# Input.net
KiCad netlist of a schematic drawn in Altium Designer
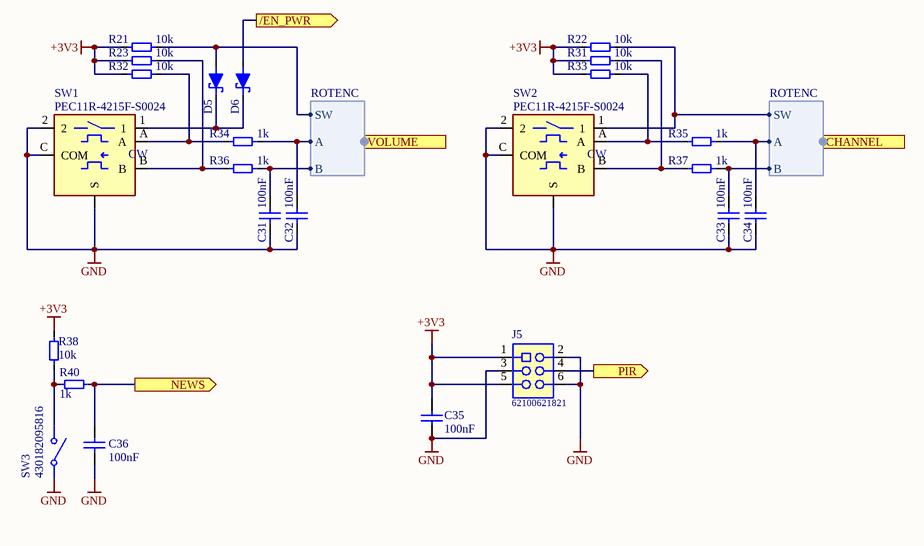
[diagram p0: Input.SchDoc]

(export (version "E")
  (design (tool "Eeschema 10.0.6"))
  (components
    (comp (ref "C31")
      (value "100nF")
      (footprint "0603-C-N")
      (description "WCAP-CSGP Multilayer Ceramic Chip Capacitor, General Purpose, size 0603, X7R, 100nF, 50VDC")
      (fields (field (name "TOLERANCE") "10%") (field (name "JLCPCB PART #") "C14663"))
      (libsource (lib "7c7 Engineering") (part "CAP-NP-2"))
    )
    (comp (ref "C32")
      (value "100nF")
      (footprint "0603-C-N")
      (description "WCAP-CSGP Multilayer Ceramic Chip Capacitor, General Purpose, size 0603, X7R, 100nF, 50VDC")
      (fields (field (name "TOLERANCE") "10%") (field (name "JLCPCB PART #") "C14663"))
      (libsource (lib "7c7 Engineering") (part "CAP-NP-2"))
    )
    (comp (ref "C33")
      (value "100nF")
      (footprint "0603-C-N")
      (description "WCAP-CSGP Multilayer Ceramic Chip Capacitor, General Purpose, size 0603, X7R, 100nF, 50VDC")
      (fields (field (name "TOLERANCE") "10%") (field (name "JLCPCB PART #") "C14663"))
      (libsource (lib "7c7 Engineering") (part "CAP-NP-2"))
    )
    (comp (ref "C34")
      (value "100nF")
      (footprint "0603-C-N")
      (description "WCAP-CSGP Multilayer Ceramic Chip Capacitor, General Purpose, size 0603, X7R, 100nF, 50VDC")
      (fields (field (name "TOLERANCE") "10%") (field (name "JLCPCB PART #") "C14663"))
      (libsource (lib "7c7 Engineering") (part "CAP-NP-2"))
    )
    (comp (ref "C35")
      (value "100nF")
      (footprint "0603-C-N")
      (description "WCAP-CSGP Multilayer Ceramic Chip Capacitor, General Purpose, size 0603, X7R, 100nF, 50VDC")
      (fields (field (name "TOLERANCE") "10%") (field (name "JLCPCB PART #") "C14663"))
      (libsource (lib "7c7 Engineering") (part "CAP-NP-2"))
    )
    (comp (ref "C36")
      (value "100nF")
      (footprint "0603-C-N")
      (description "WCAP-CSGP Multilayer Ceramic Chip Capacitor, General Purpose, size 0603, X7R, 100nF, 50VDC")
      (fields (field (name "TOLERANCE") "10%") (field (name "JLCPCB PART #") "C14663"))
      (libsource (lib "7c7 Engineering") (part "CAP-NP-2"))
    )
    (comp (ref "D5")
      (value "1PS79SB30,115")
      (footprint "FP-SOD523-MFG")
      (description "VR=40V IF=200mA 20pF")
      (fields (field (name "JLCPCB PART #") "C426690"))
      (libsource (lib "7c7 Engineering") (part "DIODE-SKY-2"))
    )
    (comp (ref "D6")
      (value "1PS79SB30,115")
      (footprint "FP-SOD523-MFG")
      (description "VR=40V IF=200mA 20pF")
      (fields (field (name "JLCPCB PART #") "C426690"))
      (libsource (lib "7c7 Engineering") (part "DIODE-SKY-2"))
    )
    (comp (ref "J5")
      (value "62100621821")
      (footprint "62100621821")
      (description "WR-PHD Socket Header, SMT, pitch 2mm, Dual Row, Vertical, 6p")
      (fields (field (name "MANUFACTURER") "Wurth Elektronik"))
      (libsource (lib "7c7 Engineering") (part "Symbol"))
    )
    (comp (ref "R21")
      (value "10k")
      (footprint "0603-R-N")
      (description "Chip Resistor, Thick Film, General Purpose, 0603, 100mW, 50V, 10 kOhm, +/-1%")
      (fields (field (name "JLCPCB PART #") "C25804") (field (name "TOLERANCE") "1%"))
      (libsource (lib "") (part "RES_1"))
    )
    (comp (ref "R22")
      (value "10k")
      (footprint "0603-R-N")
      (description "Chip Resistor, Thick Film, General Purpose, 0603, 100mW, 50V, 10 kOhm, +/-1%")
      (fields (field (name "JLCPCB PART #") "C25804") (field (name "TOLERANCE") "1%"))
      (libsource (lib "") (part "RES_1"))
    )
    (comp (ref "R23")
      (value "10k")
      (footprint "0603-R-N")
      (description "Chip Resistor, Thick Film, General Purpose, 0603, 100mW, 50V, 10 kOhm, +/-1%")
      (fields (field (name "JLCPCB PART #") "C25804") (field (name "TOLERANCE") "1%"))
      (libsource (lib "7c7 Engineering") (part "RES"))
    )
    (comp (ref "R31")
      (value "10k")
      (footprint "0603-R-N")
      (description "Chip Resistor, Thick Film, General Purpose, 0603, 100mW, 50V, 10 kOhm, +/-1%")
      (fields (field (name "JLCPCB PART #") "C25804") (field (name "TOLERANCE") "1%"))
      (libsource (lib "7c7 Engineering") (part "RES"))
    )
    (comp (ref "R32")
      (value "10k")
      (footprint "0603-R-N")
      (description "Chip Resistor, Thick Film, General Purpose, 0603, 100mW, 50V, 10 kOhm, +/-1%")
      (fields (field (name "JLCPCB PART #") "C25804") (field (name "TOLERANCE") "1%"))
      (libsource (lib "7c7 Engineering") (part "RES"))
    )
    (comp (ref "R33")
      (value "10k")
      (footprint "0603-R-N")
      (description "Chip Resistor, Thick Film, General Purpose, 0603, 100mW, 50V, 10 kOhm, +/-1%")
      (fields (field (name "JLCPCB PART #") "C25804") (field (name "TOLERANCE") "1%"))
      (libsource (lib "7c7 Engineering") (part "RES"))
    )
    (comp (ref "R34")
      (value "1k")
      (footprint "0603-R-N")
      (description "Chip Resistor, Thick Film, General Purpose, 0603, 100mW, 50V, 1 kOhm, +/-1%")
      (fields (field (name "JLCPCB PART #") "C21190") (field (name "TOLERANCE") "1%"))
      (libsource (lib "") (part "RES_1"))
    )
    (comp (ref "R35")
      (value "1k")
      (footprint "0603-R-N")
      (description "Chip Resistor, Thick Film, General Purpose, 0603, 100mW, 50V, 1 kOhm, +/-1%")
      (fields (field (name "JLCPCB PART #") "C21190") (field (name "TOLERANCE") "1%"))
      (libsource (lib "") (part "RES_1"))
    )
    (comp (ref "R36")
      (value "1k")
      (footprint "0603-R-N")
      (description "Chip Resistor, Thick Film, General Purpose, 0603, 100mW, 50V, 1 kOhm, +/-1%")
      (fields (field (name "JLCPCB PART #") "C21190") (field (name "TOLERANCE") "1%"))
      (libsource (lib "") (part "RES_1"))
    )
    (comp (ref "R37")
      (value "1k")
      (footprint "0603-R-N")
      (description "Chip Resistor, Thick Film, General Purpose, 0603, 100mW, 50V, 1 kOhm, +/-1%")
      (fields (field (name "JLCPCB PART #") "C21190") (field (name "TOLERANCE") "1%"))
      (libsource (lib "") (part "RES_1"))
    )
    (comp (ref "R38")
      (value "10k")
      (footprint "0603-R-N")
      (description "Chip Resistor, Thick Film, General Purpose, 0603, 100mW, 50V, 10 kOhm, +/-1%")
      (fields (field (name "JLCPCB PART #") "C25804") (field (name "TOLERANCE") "1%"))
      (libsource (lib "") (part "RES_1"))
    )
    (comp (ref "R40")
      (value "1k")
      (footprint "0603-R-N")
      (description "Chip Resistor, Thick Film, General Purpose, 0603, 100mW, 50V, 1 kOhm, +/-1%")
      (fields (field (name "JLCPCB PART #") "C21190") (field (name "TOLERANCE") "1%"))
      (libsource (lib "") (part "RES_2"))
    )
    (comp (ref "SW1")
      (value "PEC11R-4215F-S0024")
      (footprint "PEC11R-4215F-S0024")
      (description "Incremental Encoder 24 PPR 2 Bit Quadrature 5VDC at 10 mA IP40 PCB Mount 60RPM")
      (fields (field (name "JLCPCB PART #") "C143790"))
      (libsource (lib "7c7 Engineering") (part "482024764004"))
    )
    (comp (ref "SW2")
      (value "PEC11R-4215F-S0024")
      (footprint "PEC11R-4215F-S0024")
      (description "Incremental Encoder 24 PPR 2 Bit Quadrature 5VDC at 10 mA IP40 PCB Mount 60RPM")
      (fields (field (name "JLCPCB PART #") "C143790"))
      (libsource (lib "7c7 Engineering") (part "482024764004"))
    )
    (comp (ref "SW3")
      (value "430182095816")
      (footprint "WS-TASV_L6W6H9.5_4301x20958x6")
      (description "WS-TASV SMT Tact Switch, 12VDC, 50mA, 160g, height 9.5mm")
      (fields (field (name "MANUFACTURER") "Wurth Elektronik") (field (name "JLCPCB PART #") "C285487"))
      (libsource (lib "7c7 Engineering") (part "SW_MOM"))
    )
  )
  (nets
    (net (code "2") (name "+3V3") (class "Default")
      (node (ref "C35") (pin "2") (pinfunction "2_2") (pintype "passive"))
      (node (ref "J5") (pin "1") (pinfunction "1_1") (pintype "passive"))
      (node (ref "J5") (pin "5") (pinfunction "5_5") (pintype "passive"))
      (node (ref "R21") (pin "1") (pinfunction "1_1") (pintype "passive"))
      (node (ref "R22") (pin "1") (pinfunction "1_1") (pintype "passive"))
      (node (ref "R23") (pin "2") (pinfunction "2_2") (pintype "passive"))
      (node (ref "R31") (pin "2") (pinfunction "2_2") (pintype "passive"))
      (node (ref "R32") (pin "2") (pinfunction "2_2") (pintype "passive"))
      (node (ref "R33") (pin "2") (pinfunction "2_2") (pintype "passive"))
      (node (ref "R38") (pin "2") (pinfunction "2_2") (pintype "passive"))
    )
    (net (code "3") (name "/NEWS") (class "Default")
      (node (ref "C36") (pin "2") (pinfunction "2_2") (pintype "passive"))
      (node (ref "R40") (pin "2") (pinfunction "2_2") (pintype "passive"))
    )
    (net (code "4") (name "/PIR") (class "Default")
      (node (ref "J5") (pin "4") (pinfunction "4_4") (pintype "passive"))
    )
    (net (code "6") (name "/{slash}EN_PWR") (class "Default")
      (node (ref "D6") (pin "2") (pinfunction "A_2") (pintype "passive"))
    )
    (net (code "7") (name "GND") (class "Default")
      (node (ref "C31") (pin "1") (pinfunction "1_1") (pintype "passive"))
      (node (ref "C32") (pin "1") (pinfunction "1_1") (pintype "passive"))
      (node (ref "C33") (pin "1") (pinfunction "1_1") (pintype "passive"))
      (node (ref "C34") (pin "1") (pinfunction "1_1") (pintype "passive"))
      (node (ref "C35") (pin "1") (pinfunction "1_1") (pintype "passive"))
      (node (ref "C36") (pin "1") (pinfunction "1_1") (pintype "passive"))
      (node (ref "J5") (pin "2") (pinfunction "2_2") (pintype "passive"))
      (node (ref "J5") (pin "3") (pinfunction "3_3") (pintype "passive"))
      (node (ref "J5") (pin "6") (pinfunction "6_6") (pintype "passive"))
      (node (ref "SW1") (pin "2") (pinfunction "2_2") (pintype "passive"))
      (node (ref "SW1") (pin "C") (pinfunction "COM_C") (pintype "passive"))
      (node (ref "SW1") (pin "S") (pinfunction "S_S") (pintype "passive"))
      (node (ref "SW2") (pin "2") (pinfunction "2_2") (pintype "passive"))
      (node (ref "SW2") (pin "C") (pinfunction "COM_C") (pintype "passive"))
      (node (ref "SW2") (pin "S") (pinfunction "S_S") (pintype "passive"))
      (node (ref "SW3") (pin "1") (pinfunction "1_1") (pintype "passive"))
    )
    (net (code "8") (name "Net-(C31-Pad2)") (class "Default")
      (node (ref "C31") (pin "2") (pinfunction "2_2") (pintype "passive"))
      (node (ref "R36") (pin "2") (pinfunction "2_2") (pintype "passive"))
    )
    (net (code "9") (name "Net-(C32-Pad2)") (class "Default")
      (node (ref "C32") (pin "2") (pinfunction "2_2") (pintype "passive"))
      (node (ref "R34") (pin "2") (pinfunction "2_2") (pintype "passive"))
    )
    (net (code "10") (name "Net-(C33-Pad2)") (class "Default")
      (node (ref "C33") (pin "2") (pinfunction "2_2") (pintype "passive"))
      (node (ref "R37") (pin "2") (pinfunction "2_2") (pintype "passive"))
    )
    (net (code "11") (name "Net-(C34-Pad2)") (class "Default")
      (node (ref "C34") (pin "2") (pinfunction "2_2") (pintype "passive"))
      (node (ref "R35") (pin "2") (pinfunction "2_2") (pintype "passive"))
    )
    (net (code "12") (name "Net-(D5-A)") (class "Default")
      (node (ref "D5") (pin "2") (pinfunction "A_2") (pintype "passive"))
      (node (ref "R21") (pin "2") (pinfunction "2_2") (pintype "passive"))
    )
    (net (code "13") (name "Net-(D5-K)") (class "Default")
      (node (ref "D5") (pin "1") (pinfunction "K_1") (pintype "passive"))
      (node (ref "D6") (pin "1") (pinfunction "K_1") (pintype "passive"))
      (node (ref "SW1") (pin "1") (pinfunction "1_1") (pintype "passive"))
    )
    (net (code "14") (name "Net-(R22-Pad2)") (class "Default")
      (node (ref "R22") (pin "2") (pinfunction "2_2") (pintype "passive"))
      (node (ref "SW2") (pin "1") (pinfunction "1_1") (pintype "passive"))
    )
    (net (code "15") (name "Net-(R23-Pad1)") (class "Default")
      (node (ref "R23") (pin "1") (pinfunction "1_1") (pintype "passive"))
      (node (ref "R36") (pin "1") (pinfunction "1_1") (pintype "passive"))
      (node (ref "SW1") (pin "B") (pinfunction "B_B") (pintype "passive"))
    )
    (net (code "16") (name "Net-(R31-Pad1)") (class "Default")
      (node (ref "R31") (pin "1") (pinfunction "1_1") (pintype "passive"))
      (node (ref "R37") (pin "1") (pinfunction "1_1") (pintype "passive"))
      (node (ref "SW2") (pin "B") (pinfunction "B_B") (pintype "passive"))
    )
    (net (code "17") (name "Net-(R32-Pad1)") (class "Default")
      (node (ref "R32") (pin "1") (pinfunction "1_1") (pintype "passive"))
      (node (ref "R34") (pin "1") (pinfunction "1_1") (pintype "passive"))
      (node (ref "SW1") (pin "A") (pinfunction "A_A") (pintype "passive"))
    )
    (net (code "18") (name "Net-(R33-Pad1)") (class "Default")
      (node (ref "R33") (pin "1") (pinfunction "1_1") (pintype "passive"))
      (node (ref "R35") (pin "1") (pinfunction "1_1") (pintype "passive"))
      (node (ref "SW2") (pin "A") (pinfunction "A_A") (pintype "passive"))
    )
    (net (code "19") (name "Net-(R38-Pad1)") (class "Default")
      (node (ref "R38") (pin "1") (pinfunction "1_1") (pintype "passive"))
      (node (ref "R40") (pin "1") (pinfunction "1_1") (pintype "passive"))
      (node (ref "SW3") (pin "2") (pinfunction "2_2") (pintype "passive"))
    )
  )
)
